# datalogger-v21.net
KiCad netlist of a schematic drawn in EAGLE
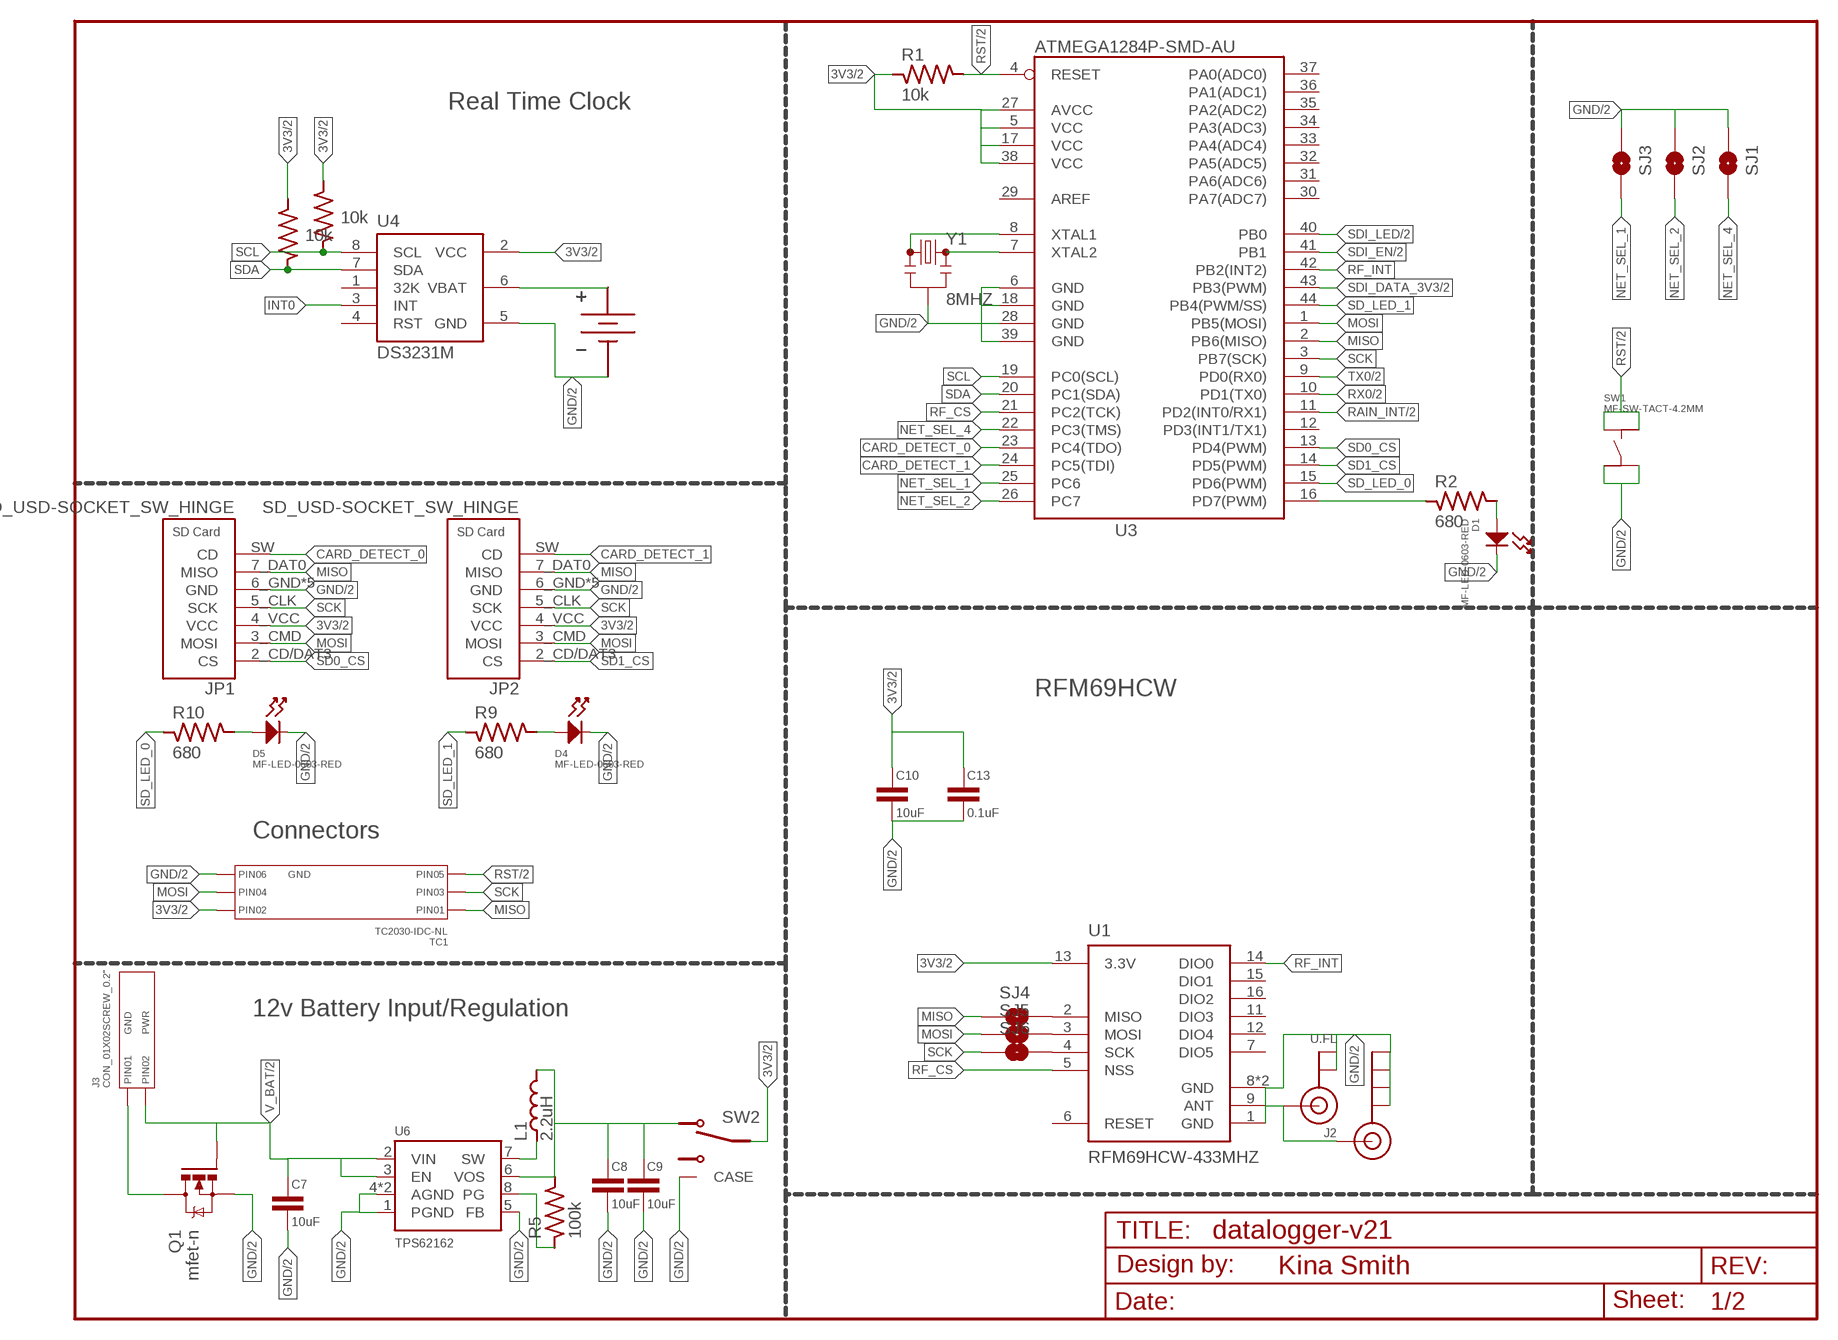
[diagram p0: schematic, sheet 1]
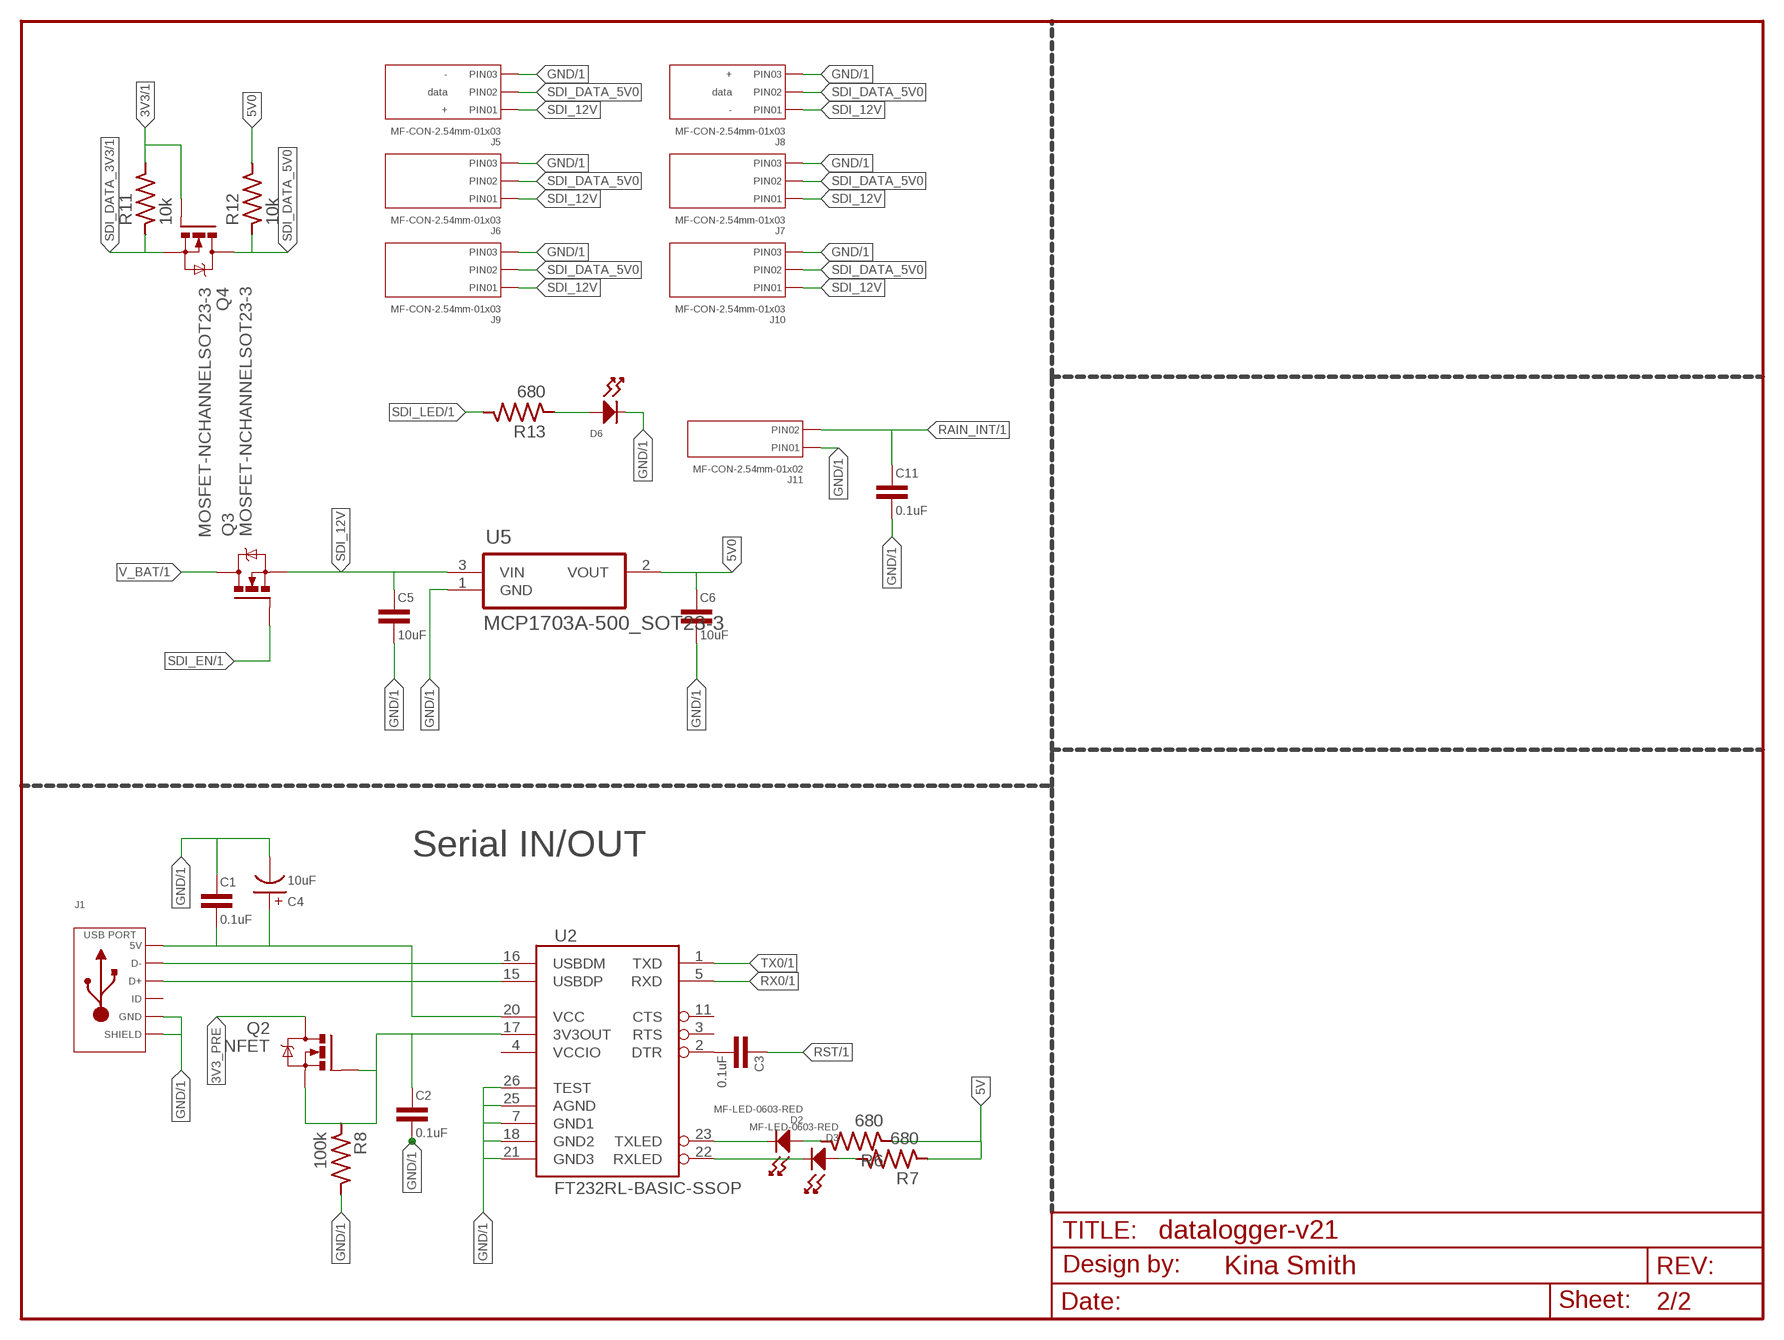
[diagram p1: schematic, sheet 2]

(export (version "E")
  (design (tool "Eeschema 10.0.6"))
  (components
    (comp (ref "BAT1")
      (value "BATTERY_HOLDER12MM")
      (footprint "eagle-import:BAT_12MM")
      (fields (field (name "PARTNO") "BK-885-TR"))
      (libsource (lib "eagle-import") (part "BATTERY_HOLDER12MM"))
    )
    (comp (ref "C7")
      (value "10uF")
      (footprint "eagle-import:C0805-N")
      (fields (field (name "PARTNO") "GRM21BR61C106KE15L"))
      (libsource (lib "eagle-import") (part "CAPACITOR_NP0805-N"))
    )
    (comp (ref "C8")
      (value "10uF")
      (footprint "eagle-import:C0805-N")
      (fields (field (name "PARTNO") "GRM21BR61C106KE15L"))
      (libsource (lib "eagle-import") (part "CAPACITOR_NP0805-N"))
    )
    (comp (ref "C9")
      (value "10uF")
      (footprint "eagle-import:C0805-N")
      (fields (field (name "PARTNO") "GRM21BR61C106KE15L"))
      (libsource (lib "eagle-import") (part "CAPACITOR_NP0805-N"))
    )
    (comp (ref "C10")
      (value "10uF")
      (footprint "eagle-import:C0805-N")
      (fields (field (name "PARTNO") "GRM21BR61C106KE15L"))
      (libsource (lib "eagle-import") (part "CAPACITOR_NP0805-N"))
    )
    (comp (ref "C13")
      (value "0.1uF")
      (footprint "eagle-import:C0603-N")
      (fields (field (name "PARTNO") "CC0603KRX7R7BB104"))
      (libsource (lib "eagle-import") (part "CAPACITOR_NP0603-N"))
    )
    (comp (ref "D1")
      (value "MF-LED-0603-RED")
      (footprint "eagle-import:LED0603")
      (fields (field (name "HOUSEPART") "YES"))
      (libsource (lib "eagle-import") (part "LED_SINGLE-0603-RED"))
    )
    (comp (ref "D4")
      (value "MF-LED-0603-RED")
      (footprint "eagle-import:LED0603")
      (fields (field (name "HOUSEPART") "YES"))
      (libsource (lib "eagle-import") (part "LED_SINGLE-0603-RED"))
    )
    (comp (ref "D5")
      (value "MF-LED-0603-RED")
      (footprint "eagle-import:LED0603")
      (fields (field (name "HOUSEPART") "YES"))
      (libsource (lib "eagle-import") (part "LED_SINGLE-0603-RED"))
    )
    (comp (ref "FRAME1")
      (value "FRAME-LETTERNO_PACKAGE")
      (footprint "eagle-import:DUMMY")
      (fields (field (name "DESIGNER") "Nobody"))
      (libsource (lib "eagle-import") (part "FRAME-LETTERNO_PACKAGE"))
    )
    (comp (ref "J2")
      (value "U.FL")
      (footprint "eagle-import:ADAFRUIT_U.FL")
      (fields (field (name "PARTNO") "U.FL-R-SMT-1(10)"))
      (libsource (lib "eagle-import") (part "ANTENNA_U.FL"))
    )
    (comp (ref "J3")
      (value "CON_01X02SCREW_0.2\"")
      (footprint "eagle-import:SCREW_TERM_2POS")
      (fields (field (name "PARTNO") "1729128"))
      (libsource (lib "eagle-import") (part "CON_01X02SCREW_0.2{dblquote}"))
    )
    (comp (ref "J4")
      (value "ANTENNA_SMA_EDGE")
      (footprint "eagle-import:SMA-EDGE")
      (fields (field (name "PARTNO") "EMPCB.SMAFSTJ.B.HT"))
      (libsource (lib "eagle-import") (part "ANTENNA_SMA_EDGE"))
    )
    (comp (ref "JP1")
      (value "SD_USD-SOCKET_SW_HINGE")
      (footprint "eagle-import:SD_MICRO_HIROSE-DM3C")
      (fields (field (name "PARTNO") "DM3CS-SF "))
      (libsource (lib "eagle-import") (part "SD_USD-SOCKET_SW_HINGE"))
    )
    (comp (ref "JP2")
      (value "SD_USD-SOCKET_SW_HINGE")
      (footprint "eagle-import:SD_MICRO_HIROSE-DM3C")
      (fields (field (name "PARTNO") "DM3CS-SF "))
      (libsource (lib "eagle-import") (part "SD_USD-SOCKET_SW_HINGE"))
    )
    (comp (ref "L1")
      (value "2.2uH")
      (footprint "eagle-import:L2520")
      (fields (field (name "PARTNO") "VLS252012T-2R2M1R3 "))
      (libsource (lib "eagle-import") (part "INDUCTOR2520"))
    )
    (comp (ref "Q1")
      (value "mfet-n")
      (footprint "eagle-import:SOT23-3")
      (fields (field (name "PARTNO") "SI2312BDS-T1-GE3"))
      (libsource (lib "eagle-import") (part "MOSFET-NCHANNELSOT23-3"))
    )
    (comp (ref "R1")
      (value "10k")
      (footprint "eagle-import:R0603-N")
      (fields (field (name "PARTNO") "RC0603FR-0710KL"))
      (libsource (lib "eagle-import") (part "RESISTOR0603-N"))
    )
    (comp (ref "R2")
      (value "680")
      (footprint "eagle-import:R0603-N")
      (fields (field (name "PARTNO") "RC0603FR-0710KL"))
      (libsource (lib "eagle-import") (part "RESISTOR0603-N"))
    )
    (comp (ref "R3")
      (value "10k")
      (footprint "eagle-import:R0603-N")
      (fields (field (name "PARTNO") "RC0603FR-0710KL"))
      (libsource (lib "eagle-import") (part "RESISTOR0603-N"))
    )
    (comp (ref "R4")
      (value "10k")
      (footprint "eagle-import:R0603-N")
      (fields (field (name "PARTNO") "RC0603FR-0710KL"))
      (libsource (lib "eagle-import") (part "RESISTOR0603-N"))
    )
    (comp (ref "R5")
      (value "100k")
      (footprint "eagle-import:R0603-N")
      (fields (field (name "PARTNO") "RC0603FR-07100KL"))
      (libsource (lib "eagle-import") (part "RESISTOR0603-N"))
    )
    (comp (ref "R9")
      (value "680")
      (footprint "eagle-import:R0603-N")
      (fields (field (name "PARTNO") "RC0603FR-0710KL"))
      (libsource (lib "eagle-import") (part "RESISTOR0603-N"))
    )
    (comp (ref "R10")
      (value "680")
      (footprint "eagle-import:R0603-N")
      (fields (field (name "PARTNO") "RC0603FR-0710KL"))
      (libsource (lib "eagle-import") (part "RESISTOR0603-N"))
    )
    (comp (ref "SJ1")
      (value "JUMPER-PAD-2-NOYES_SILK")
      (footprint "eagle-import:PAD-JUMPER-2-NO_YES_SILK")
      (fields (field (name "PARTNO") "NA"))
      (libsource (lib "eagle-import") (part "JUMPER-PAD-2-NOYES_SILK"))
    )
    (comp (ref "SJ2")
      (value "JUMPER-PAD-2-NOYES_SILK")
      (footprint "eagle-import:PAD-JUMPER-2-NO_YES_SILK")
      (fields (field (name "PARTNO") "NA"))
      (libsource (lib "eagle-import") (part "JUMPER-PAD-2-NOYES_SILK"))
    )
    (comp (ref "SJ3")
      (value "JUMPER-PAD-2-NOYES_SILK")
      (footprint "eagle-import:PAD-JUMPER-2-NO_YES_SILK")
      (fields (field (name "PARTNO") "NA"))
      (libsource (lib "eagle-import") (part "JUMPER-PAD-2-NOYES_SILK"))
    )
    (comp (ref "SJ4")
      (value "JUMPER-PAD-2-NOYES_SILK")
      (footprint "eagle-import:PAD-JUMPER-2-NO_YES_SILK")
      (fields (field (name "PARTNO") "NA"))
      (libsource (lib "eagle-import") (part "JUMPER-PAD-2-NOYES_SILK"))
    )
    (comp (ref "SJ5")
      (value "JUMPER-PAD-2-NOYES_SILK")
      (footprint "eagle-import:PAD-JUMPER-2-NO_YES_SILK")
      (fields (field (name "PARTNO") "NA"))
      (libsource (lib "eagle-import") (part "JUMPER-PAD-2-NOYES_SILK"))
    )
    (comp (ref "SJ6")
      (value "JUMPER-PAD-2-NOYES_SILK")
      (footprint "eagle-import:PAD-JUMPER-2-NO_YES_SILK")
      (fields (field (name "PARTNO") "NA"))
      (libsource (lib "eagle-import") (part "JUMPER-PAD-2-NOYES_SILK"))
    )
    (comp (ref "SW1")
      (value "MF-SW-TACT-4.2MM")
      (footprint "eagle-import:TACT4.2MM")
      (fields (field (name "HOUSEPART") "YES") (field (name "PARTNO") "PTS810 SJM 250 SMTR LFS"))
      (libsource (lib "eagle-import") (part "TACT_4.2MM"))
    )
    (comp (ref "SW2")
      (value "SWITCH_SPDT_SMD_ES01MSABE")
      (footprint "eagle-import:SPDT_ES01MSABE")
      (fields (field (name "PARTNO") "ES01MSABE"))
      (libsource (lib "eagle-import") (part "SWITCH_SPDT_SMD_ES01MSABE"))
    )
    (comp (ref "TC1")
      (value "TC2030-IDC-NL")
      (footprint "eagle-import:TC2030-IDC-NL")
      (fields (field (name "HOUSEPART") "NO") (field (name "PARTNO") "NA") (field (name "PARTNO_1") "NA"))
      (libsource (lib "eagle-import") (part "CON_02X03_TC2030-IDC-NL_AVRISP"))
    )
    (comp (ref "U1")
      (value "RFM69HCW-433MHZ")
      (footprint "eagle-import:RFM69HCW-XXXS2")
      (fields (field (name "PARTNO") "COM-13910"))
      (libsource (lib "eagle-import") (part "RFM69HCW-433MHZ"))
    )
    (comp (ref "U3")
      (value "ATMEGA1284P-SMD-AU")
      (footprint "eagle-import:TQFP44")
      (libsource (lib "eagle-import") (part "ATMEGA1284P-SMD-AU"))
    )
    (comp (ref "U4")
      (value "DS3231M")
      (footprint "eagle-import:SO08")
      (fields (field (name "PARTNO") "DS3231MZ/V+"))
      (libsource (lib "eagle-import") (part "DS3231M"))
    )
    (comp (ref "U6")
      (value "TPS62162")
      (footprint "eagle-import:WSON-8")
      (fields (field (name "PARTNO") "TPS62162DSGR"))
      (libsource (lib "eagle-import") (part "TPS62162"))
    )
    (comp (ref "Y1")
      (value "8MHZ")
      (footprint "eagle-import:RESONATOR-SMD")
      (fields (field (name "PARTNO") "CSTCE8M00G55-R0"))
      (libsource (lib "eagle-import") (part "RESONATOR8MHZ"))
    )
    (comp (ref "C1")
      (value "0.1uF")
      (footprint "eagle-import:C0603-N")
      (libsource (lib "eagle-import") (part "CAPACITOR_NP0603-N"))
    )
    (comp (ref "C2")
      (value "0.1uF")
      (footprint "eagle-import:C0603-N")
      (libsource (lib "eagle-import") (part "CAPACITOR_NP0603-N"))
    )
    (comp (ref "C3")
      (value "0.1uF")
      (footprint "eagle-import:C0603-N")
      (libsource (lib "eagle-import") (part "CAPACITOR_NP0603-N"))
    )
    (comp (ref "C4")
      (value "10uF")
      (footprint "eagle-import:EIA3216")
      (libsource (lib "eagle-import") (part "CAPACITOR_P_3216"))
    )
    (comp (ref "C5")
      (value "10uF")
      (footprint "eagle-import:C0805-N")
      (libsource (lib "eagle-import") (part "CAPACITOR_NP0805-N"))
    )
    (comp (ref "C6")
      (value "10uF")
      (footprint "eagle-import:C0805-N")
      (libsource (lib "eagle-import") (part "CAPACITOR_NP0805-N"))
    )
    (comp (ref "C11")
      (value "0.1uF")
      (footprint "eagle-import:C0603-N")
      (libsource (lib "eagle-import") (part "CAPACITOR_NP0603-N"))
    )
    (comp (ref "D2")
      (value "MF-LED-0603-RED")
      (footprint "eagle-import:LED0603")
      (fields (field (name "HOUSEPART") "YES"))
      (libsource (lib "eagle-import") (part "LED_SINGLE-0603-RED"))
    )
    (comp (ref "D3")
      (value "MF-LED-0603-RED")
      (footprint "eagle-import:LED0603")
      (fields (field (name "HOUSEPART") "YES"))
      (libsource (lib "eagle-import") (part "LED_SINGLE-0603-RED"))
    )
    (comp (ref "D6")
      (value "LED_SINGLE-0603")
      (footprint "eagle-import:LED0603")
      (fields (field (name "HOUSEPART") "NO"))
      (libsource (lib "eagle-import") (part "LED_SINGLE-0603"))
    )
    (comp (ref "FRAME3")
      (value "FRAME-LETTERNO_PACKAGE")
      (footprint "eagle-import:DUMMY")
      (fields (field (name "DESIGNER") "Nobody"))
      (libsource (lib "eagle-import") (part "FRAME-LETTERNO_PACKAGE"))
    )
    (comp (ref "J1")
      (value "USB-5PIN_B-MICRO_R/A_STRONG")
      (footprint "eagle-import:USB-MICRO-MOLEX-105017-0001")
      (fields (field (name "PARTNO") "1050170001"))
      (libsource (lib "eagle-import") (part "USB-5PIN_B-MICRO_R/A_STRONG"))
    )
    (comp (ref "J5")
      (value "MF-CON-2.54mm-01x03")
      (footprint "eagle-import:PTH_2.54MM_01X03")
      (fields
        (field (name "HOUSEPART") "YES")
        (field (name "LABEL01") "+")
        (field (name "LABEL02") "data")
        (field (name "LABEL03") "-")
      )
      (libsource (lib "eagle-import") (part "CON_01X03_PTH_2.54MM"))
    )
    (comp (ref "J6")
      (value "MF-CON-2.54mm-01x03")
      (footprint "eagle-import:PTH_2.54MM_01X03")
      (fields (field (name "HOUSEPART") "YES"))
      (libsource (lib "eagle-import") (part "CON_01X03_PTH_2.54MM"))
    )
    (comp (ref "J7")
      (value "MF-CON-2.54mm-01x03")
      (footprint "eagle-import:PTH_2.54MM_01X03")
      (fields (field (name "HOUSEPART") "YES"))
      (libsource (lib "eagle-import") (part "CON_01X03_PTH_2.54MM"))
    )
    (comp (ref "J8")
      (value "MF-CON-2.54mm-01x03")
      (footprint "eagle-import:PTH_2.54MM_01X03")
      (fields
        (field (name "HOUSEPART") "YES")
        (field (name "LABEL01") "-")
        (field (name "LABEL02") "data")
        (field (name "LABEL03") "+")
      )
      (libsource (lib "eagle-import") (part "CON_01X03_PTH_2.54MM"))
    )
    (comp (ref "J9")
      (value "MF-CON-2.54mm-01x03")
      (footprint "eagle-import:PTH_2.54MM_01X03")
      (fields (field (name "HOUSEPART") "YES"))
      (libsource (lib "eagle-import") (part "CON_01X03_PTH_2.54MM"))
    )
    (comp (ref "J10")
      (value "MF-CON-2.54mm-01x03")
      (footprint "eagle-import:PTH_2.54MM_01X03")
      (fields (field (name "HOUSEPART") "YES"))
      (libsource (lib "eagle-import") (part "CON_01X03_PTH_2.54MM"))
    )
    (comp (ref "J11")
      (value "MF-CON-2.54mm-01x02")
      (footprint "eagle-import:PTH_2.54MM_01X02")
      (fields (field (name "HOUSEPART") "YES"))
      (libsource (lib "eagle-import") (part "CON_01X02_PTH_2.54MM"))
    )
    (comp (ref "Q2")
      (value "NFET")
      (footprint "eagle-import:SOT23-3")
      (libsource (lib "eagle-import") (part "MOSFET-NCHANNELSOT23-3"))
    )
    (comp (ref "Q3")
      (value "MOSFET-NCHANNELSOT23-3")
      (footprint "eagle-import:SOT23-3")
      (libsource (lib "eagle-import") (part "MOSFET-NCHANNELSOT23-3"))
    )
    (comp (ref "Q4")
      (value "MOSFET-NCHANNELSOT23-3")
      (footprint "eagle-import:SOT23-3")
      (libsource (lib "eagle-import") (part "MOSFET-NCHANNELSOT23-3"))
    )
    (comp (ref "R6")
      (value "680")
      (footprint "eagle-import:R0603-N")
      (libsource (lib "eagle-import") (part "RESISTOR0603-N"))
    )
    (comp (ref "R7")
      (value "680")
      (footprint "eagle-import:R0603-N")
      (libsource (lib "eagle-import") (part "RESISTOR0603-N"))
    )
    (comp (ref "R8")
      (value "100k")
      (footprint "eagle-import:R0603-N")
      (libsource (lib "eagle-import") (part "RESISTOR0603-N"))
    )
    (comp (ref "R11")
      (value "10k")
      (footprint "eagle-import:R0603-N")
      (libsource (lib "eagle-import") (part "RESISTOR0603-N"))
    )
    (comp (ref "R12")
      (value "10k")
      (footprint "eagle-import:R0603-N")
      (libsource (lib "eagle-import") (part "RESISTOR0603-N"))
    )
    (comp (ref "R13")
      (value "680")
      (footprint "eagle-import:R0603-N")
      (libsource (lib "eagle-import") (part "RESISTOR0603-N"))
    )
    (comp (ref "U2")
      (value "FT232RL-BASIC-SSOP")
      (footprint "eagle-import:SSOP28")
      (libsource (lib "eagle-import") (part "FT232RL-BASIC-SSOP"))
    )
    (comp (ref "U5")
      (value "MCP1703A-500_SOT23-3")
      (footprint "eagle-import:SOT23-3")
      (fields (field (name "PARTNO") "MCP1703AT-5002E/CB"))
      (libsource (lib "eagle-import") (part "MCP1703A-500_SOT23-3"))
    )
  )
  (nets
    (net (code "1") (name "3V3") (class "Default")
      (node (ref "C10") (pin "1") (pinfunction "1_1") (pintype "passive"))
      (node (ref "C13") (pin "1") (pinfunction "1_1") (pintype "passive"))
      (node (ref "JP1") (pin "4_VCC") (pinfunction "VCC_4_VCC") (pintype "bidirectional"))
      (node (ref "JP2") (pin "4_VCC") (pinfunction "VCC_4_VCC") (pintype "bidirectional"))
      (node (ref "Q4") (pin "1") (pinfunction "G_1") (pintype "passive"))
      (node (ref "R1") (pin "1") (pinfunction "P$1_1") (pintype "passive"))
      (node (ref "R11") (pin "2") (pinfunction "P$2_2") (pintype "passive"))
      (node (ref "R3") (pin "2") (pinfunction "P$2_2") (pintype "passive"))
      (node (ref "R4") (pin "2") (pinfunction "P$2_2") (pintype "passive"))
      (node (ref "SW2") (pin "2") (pinfunction "COM_2") (pintype "bidirectional"))
      (node (ref "TC1") (pin "P$2") (pinfunction "PIN2_P$2") (pintype "bidirectional"))
      (node (ref "U1") (pin "13") (pinfunction "3.3V_13") (pintype "power_in"))
      (node (ref "U3") (pin "17") (pinfunction "VCC_17") (pintype "bidirectional"))
      (node (ref "U3") (pin "27") (pinfunction "AVCC_27") (pintype "bidirectional"))
      (node (ref "U3") (pin "38") (pinfunction "VCC_38") (pintype "bidirectional"))
      (node (ref "U3") (pin "5") (pinfunction "VCC_5") (pintype "bidirectional"))
      (node (ref "U4") (pin "2") (pinfunction "VCC_2") (pintype "power_in"))
    )
    (net (code "2") (name "3V3_PRE") (class "Default")
      (node (ref "C8") (pin "1") (pinfunction "1_1") (pintype "passive"))
      (node (ref "C9") (pin "1") (pinfunction "1_1") (pintype "passive"))
      (node (ref "L1") (pin "P$2") (pinfunction "P$2_P$2") (pintype "passive"))
      (node (ref "Q2") (pin "3") (pinfunction "D_3") (pintype "passive"))
      (node (ref "R5") (pin "2") (pinfunction "P$2_2") (pintype "passive"))
      (node (ref "SW2") (pin "1") (pinfunction "1_1") (pintype "bidirectional"))
      (node (ref "U6") (pin "6") (pinfunction "VOS_6") (pintype "bidirectional"))
    )
    (net (code "3") (name "5V") (class "Default")
      (node (ref "C1") (pin "2") (pinfunction "2_2") (pintype "passive"))
      (node (ref "C4") (pin "A") (pinfunction "POS_A") (pintype "passive"))
      (node (ref "J1") (pin "1") (pinfunction "5V_1") (pintype "power_in"))
      (node (ref "R6") (pin "1") (pinfunction "P$1_1") (pintype "passive"))
      (node (ref "R7") (pin "1") (pinfunction "P$1_1") (pintype "passive"))
      (node (ref "U2") (pin "20") (pinfunction "VCC_20") (pintype "power_in"))
    )
    (net (code "4") (name "5V0") (class "Default")
      (node (ref "C6") (pin "1") (pinfunction "1_1") (pintype "passive"))
      (node (ref "R12") (pin "2") (pinfunction "P$2_2") (pintype "passive"))
      (node (ref "U5") (pin "2") (pinfunction "VOUT_2") (pintype "output"))
    )
    (net (code "5") (name "CARD_DETECT_0") (class "Default")
      (node (ref "JP1") (pin "SW") (pinfunction "CD_SW") (pintype "bidirectional"))
      (node (ref "U3") (pin "23") (pinfunction "PC4(TDO)_23") (pintype "bidirectional"))
    )
    (net (code "6") (name "CARD_DETECT_1") (class "Default")
      (node (ref "JP2") (pin "SW") (pinfunction "CD_SW") (pintype "bidirectional"))
      (node (ref "U3") (pin "24") (pinfunction "PC5(TDI)_24") (pintype "bidirectional"))
    )
    (net (code "7") (name "GND") (class "Default")
      (node (ref "BAT1") (pin "GND") (pinfunction "GND_GND") (pintype "bidirectional"))
      (node (ref "C1") (pin "1") (pinfunction "1_1") (pintype "passive"))
      (node (ref "C10") (pin "2") (pinfunction "2_2") (pintype "passive"))
      (node (ref "C11") (pin "2") (pinfunction "2_2") (pintype "passive"))
      (node (ref "C13") (pin "2") (pinfunction "2_2") (pintype "passive"))
      (node (ref "C2") (pin "2") (pinfunction "2_2") (pintype "passive"))
      (node (ref "C4") (pin "C") (pinfunction "NEG_C") (pintype "passive"))
      (node (ref "C5") (pin "2") (pinfunction "2_2") (pintype "passive"))
      (node (ref "C6") (pin "2") (pinfunction "2_2") (pintype "passive"))
      (node (ref "C7") (pin "2") (pinfunction "2_2") (pintype "passive"))
      (node (ref "C8") (pin "2") (pinfunction "2_2") (pintype "passive"))
      (node (ref "C9") (pin "2") (pinfunction "2_2") (pintype "passive"))
      (node (ref "D1") (pin "CATHODE") (pinfunction "CATHODE_CATHODE") (pintype "power_in"))
      (node (ref "D4") (pin "CATHODE") (pinfunction "CATHODE_CATHODE") (pintype "power_in"))
      (node (ref "D5") (pin "CATHODE") (pinfunction "CATHODE_CATHODE") (pintype "power_in"))
      (node (ref "D6") (pin "CATHODE") (pinfunction "CATHODE_CATHODE") (pintype "power_in"))
      (node (ref "J1") (pin "5") (pinfunction "GND_5") (pintype "power_in"))
      (node (ref "J1") (pin "P$1") (pinfunction "SLD_P$1") (pintype "power_in"))
      (node (ref "J1") (pin "P$2") (pinfunction "SLD_P$2") (pintype "power_in"))
      (node (ref "J1") (pin "P$3") (pinfunction "SLD_P$3") (pintype "power_in"))
      (node (ref "J1") (pin "P$4") (pinfunction "SLD_P$4") (pintype "power_in"))
      (node (ref "J1") (pin "P$5") (pinfunction "SLD_P$5") (pintype "power_in"))
      (node (ref "J1") (pin "P$6") (pinfunction "SLD_P$6") (pintype "power_in"))
      (node (ref "J10") (pin "P$3") (pinfunction "PIN3_P$3") (pintype "bidirectional"))
      (node (ref "J11") (pin "P$1") (pinfunction "PIN1_P$1") (pintype "bidirectional"))
      (node (ref "J2") (pin "1") (pinfunction "GND_1") (pintype "passive"))
      (node (ref "J2") (pin "2") (pinfunction "GND_2") (pintype "passive"))
      (node (ref "J4") (pin "GND@0") (pinfunction "GND_GND@0") (pintype "bidirectional"))
      (node (ref "J4") (pin "GND@1") (pinfunction "GND_GND@1") (pintype "bidirectional"))
      (node (ref "J4") (pin "GND@2") (pinfunction "GND_GND@2") (pintype "bidirectional"))
      (node (ref "J4") (pin "GND@3") (pinfunction "GND_GND@3") (pintype "bidirectional"))
      (node (ref "J5") (pin "P$3") (pinfunction "PIN3_P$3") (pintype "bidirectional"))
      (node (ref "J6") (pin "P$3") (pinfunction "PIN3_P$3") (pintype "bidirectional"))
      (node (ref "J7") (pin "P$3") (pinfunction "PIN3_P$3") (pintype "bidirectional"))
      (node (ref "J8") (pin "P$3") (pinfunction "PIN3_P$3") (pintype "bidirectional"))
      (node (ref "J9") (pin "P$3") (pinfunction "PIN3_P$3") (pintype "bidirectional"))
      (node (ref "JP1") (pin "6_GND") (pinfunction "GND_6_GND") (pintype "bidirectional"))
      (node (ref "JP1") (pin "GND1") (pinfunction "GND_GND1") (pintype "bidirectional"))
      (node (ref "JP1") (pin "GND2") (pinfunction "GND_GND2") (pintype "bidirectional"))
      (node (ref "JP1") (pin "GND3") (pinfunction "GND_GND3") (pintype "bidirectional"))
      (node (ref "JP1") (pin "GND4") (pinfunction "GND_GND4") (pintype "bidirectional"))
      (node (ref "JP2") (pin "6_GND") (pinfunction "GND_6_GND") (pintype "bidirectional"))
      (node (ref "JP2") (pin "GND1") (pinfunction "GND_GND1") (pintype "bidirectional"))
      (node (ref "JP2") (pin "GND2") (pinfunction "GND_GND2") (pintype "bidirectional"))
      (node (ref "JP2") (pin "GND3") (pinfunction "GND_GND3") (pintype "bidirectional"))
      (node (ref "JP2") (pin "GND4") (pinfunction "GND_GND4") (pintype "bidirectional"))
      (node (ref "Q1") (pin "2") (pinfunction "S_2") (pintype "passive"))
      (node (ref "R8") (pin "2") (pinfunction "P$2_2") (pintype "passive"))
      (node (ref "SJ1") (pin "1") (pinfunction "1_1") (pintype "passive"))
      (node (ref "SJ2") (pin "1") (pinfunction "1_1") (pintype "passive"))
      (node (ref "SJ3") (pin "1") (pinfunction "1_1") (pintype "passive"))
      (node (ref "SW1") (pin "P$3") (pinfunction "P$3_P$3") (pintype "bidirectional"))
      (node (ref "SW1") (pin "P$4") (pinfunction "P$4_P$4") (pintype "bidirectional"))
      (node (ref "SW2") (pin "GND") (pinfunction "CASE_GND") (pintype "bidirectional"))
      (node (ref "SW2") (pin "GND1") (pinfunction "CASE_GND1") (pintype "bidirectional"))
      (node (ref "TC1") (pin "P$6") (pinfunction "PIN6_P$6") (pintype "bidirectional"))
      (node (ref "U1") (pin "1") (pinfunction "GND_1") (pintype "power_in"))
      (node (ref "U1") (pin "10") (pinfunction "GND_10") (pintype "power_in"))
      (node (ref "U1") (pin "8") (pinfunction "GND_8") (pintype "power_in"))
      (node (ref "U2") (pin "18") (pinfunction "GND2_18") (pintype "power_in"))
      (node (ref "U2") (pin "21") (pinfunction "GND3_21") (pintype "power_in"))
      (node (ref "U2") (pin "25") (pinfunction "AGND_25") (pintype "power_in"))
      (node (ref "U2") (pin "26") (pinfunction "TEST_26") (pintype "input"))
      (node (ref "U2") (pin "7") (pinfunction "GND1_7") (pintype "power_in"))
      (node (ref "U3") (pin "18") (pinfunction "GND_18") (pintype "bidirectional"))
      (node (ref "U3") (pin "28") (pinfunction "GND_28") (pintype "bidirectional"))
      (node (ref "U3") (pin "39") (pinfunction "GND_39") (pintype "bidirectional"))
      (node (ref "U3") (pin "6") (pinfunction "GND_6") (pintype "bidirectional"))
      (node (ref "U4") (pin "5") (pinfunction "GND_5") (pintype "power_in"))
      (node (ref "U5") (pin "1") (pinfunction "GND_1") (pintype "passive"))
      (node (ref "U6") (pin "1") (pinfunction "PGND_1") (pintype "bidirectional"))
      (node (ref "U6") (pin "4") (pinfunction "AGND_4") (pintype "bidirectional"))
      (node (ref "U6") (pin "5") (pinfunction "FB_5") (pintype "bidirectional"))
      (node (ref "U6") (pin "P$9") (pinfunction "AGND_P$9") (pintype "bidirectional"))
      (node (ref "Y1") (pin "2") (pinfunction "2_2") (pintype "passive"))
    )
    (net (code "8") (name "INT0") (class "Default")
      (node (ref "U4") (pin "3") (pinfunction "INT_3") (pintype "bidirectional"))
    )
    (net (code "9") (name "MISO") (class "Default")
      (node (ref "JP1") (pin "7_DAT0") (pinfunction "MISO_7_DAT0") (pintype "bidirectional"))
      (node (ref "JP2") (pin "7_DAT0") (pinfunction "MISO_7_DAT0") (pintype "bidirectional"))
      (node (ref "SJ4") (pin "1") (pinfunction "1_1") (pintype "passive"))
      (node (ref "TC1") (pin "P$1") (pinfunction "PIN1_P$1") (pintype "bidirectional"))
      (node (ref "U3") (pin "2") (pinfunction "PB6(MISO)_2") (pintype "bidirectional"))
    )
    (net (code "10") (name "MOSI") (class "Default")
      (node (ref "JP1") (pin "3_CMD") (pinfunction "MOSI_3_CMD") (pintype "bidirectional"))
      (node (ref "JP2") (pin "3_CMD") (pinfunction "MOSI_3_CMD") (pintype "bidirectional"))
      (node (ref "SJ5") (pin "1") (pinfunction "1_1") (pintype "passive"))
      (node (ref "TC1") (pin "P$4") (pinfunction "PIN4_P$4") (pintype "bidirectional"))
      (node (ref "U3") (pin "1") (pinfunction "PB5(MOSI)_1") (pintype "bidirectional"))
    )
    (net (code "11") (name "NET_SEL_1") (class "Default")
      (node (ref "SJ3") (pin "2") (pinfunction "2_2") (pintype "passive"))
      (node (ref "U3") (pin "25") (pinfunction "PC6_25") (pintype "bidirectional"))
    )
    (net (code "12") (name "NET_SEL_2") (class "Default")
      (node (ref "SJ2") (pin "2") (pinfunction "2_2") (pintype "passive"))
      (node (ref "U3") (pin "26") (pinfunction "PC7_26") (pintype "bidirectional"))
    )
    (net (code "13") (name "NET_SEL_4") (class "Default")
      (node (ref "SJ1") (pin "2") (pinfunction "2_2") (pintype "passive"))
      (node (ref "U3") (pin "22") (pinfunction "PC3(TMS)_22") (pintype "bidirectional"))
    )
    (net (code "14") (name "Net-(J1-D+)") (class "Default")
      (node (ref "J1") (pin "3") (pinfunction "D+_3") (pintype "bidirectional"))
      (node (ref "U2") (pin "15") (pinfunction "USBDP_15") (pintype "bidirectional"))
    )
    (net (code "15") (name "Net-(J1-D-)") (class "Default")
      (node (ref "J1") (pin "2") (pinfunction "D-_2") (pintype "bidirectional"))
      (node (ref "U2") (pin "16") (pinfunction "USBDM_16") (pintype "bidirectional"))
    )
    (net (code "16") (name "Net-(J2-SIGNAL)") (class "Default")
      (node (ref "J2") (pin "3") (pinfunction "SIGNAL_3") (pintype "passive"))
      (node (ref "J4") (pin "SIG") (pinfunction "SIGNAL_SIG") (pintype "bidirectional"))
      (node (ref "U1") (pin "9") (pinfunction "ANT_9") (pintype "passive"))
    )
    (net (code "17") (name "Net-(J3-PIN1)") (class "Default")
      (node (ref "J3") (pin "GND") (pinfunction "PIN1_GND") (pintype "bidirectional"))
      (node (ref "Q1") (pin "3") (pinfunction "D_3") (pintype "passive"))
    )
    (net (code "18") (name "Net-(Q2-G)") (class "Default")
      (node (ref "C2") (pin "1") (pinfunction "1_1") (pintype "passive"))
      (node (ref "Q2") (pin "1") (pinfunction "G_1") (pintype "passive"))
      (node (ref "Q2") (pin "2") (pinfunction "S_2") (pintype "passive"))
      (node (ref "R8") (pin "1") (pinfunction "P$1_1") (pintype "passive"))
      (node (ref "U2") (pin "17") (pinfunction "3V3OUT_17") (pintype "output"))
    )
    (net (code "19") (name "Net-(R2-P$1)") (class "Default")
      (node (ref "R2") (pin "1") (pinfunction "P$1_1") (pintype "passive"))
      (node (ref "U3") (pin "16") (pinfunction "PD7(PWM)_16") (pintype "bidirectional"))
    )
    (net (code "20") (name "Net-(R2-P$2)") (class "Default")
      (node (ref "D1") (pin "ANODE") (pinfunction "ANODE_ANODE") (pintype "power_in"))
      (node (ref "R2") (pin "2") (pinfunction "P$2_2") (pintype "passive"))
    )
    (net (code "21") (name "Net-(R5-P$1)") (class "Default")
      (node (ref "R5") (pin "1") (pinfunction "P$1_1") (pintype "passive"))
      (node (ref "U6") (pin "8") (pinfunction "PG_8") (pintype "bidirectional"))
    )
    (net (code "22") (name "Net-(R6-P$2)") (class "Default")
      (node (ref "D2") (pin "ANODE") (pinfunction "ANODE_ANODE") (pintype "power_in"))
      (node (ref "R6") (pin "2") (pinfunction "P$2_2") (pintype "passive"))
    )
    (net (code "23") (name "Net-(R7-P$2)") (class "Default")
      (node (ref "D3") (pin "ANODE") (pinfunction "ANODE_ANODE") (pintype "power_in"))
      (node (ref "R7") (pin "2") (pinfunction "P$2_2") (pintype "passive"))
    )
    (net (code "24") (name "Net-(R9-P$2)") (class "Default")
      (node (ref "D4") (pin "ANODE") (pinfunction "ANODE_ANODE") (pintype "power_in"))
      (node (ref "R9") (pin "2") (pinfunction "P$2_2") (pintype "passive"))
    )
    (net (code "25") (name "Net-(R10-P$2)") (class "Default")
      (node (ref "D5") (pin "ANODE") (pinfunction "ANODE_ANODE") (pintype "power_in"))
      (node (ref "R10") (pin "2") (pinfunction "P$2_2") (pintype "passive"))
    )
    (net (code "26") (name "Net-(R13-P$1)") (class "Default")
      (node (ref "D6") (pin "ANODE") (pinfunction "ANODE_ANODE") (pintype "power_in"))
      (node (ref "R13") (pin "1") (pinfunction "P$1_1") (pintype "passive"))
    )
    (net (code "27") (name "Net-(U1-MISO)") (class "Default")
      (node (ref "SJ4") (pin "2") (pinfunction "2_2") (pintype "passive"))
      (node (ref "U1") (pin "2") (pinfunction "MISO_2") (pintype "bidirectional"))
    )
    (net (code "28") (name "Net-(U1-MOSI)") (class "Default")
      (node (ref "SJ5") (pin "2") (pinfunction "2_2") (pintype "passive"))
      (node (ref "U1") (pin "3") (pinfunction "MOSI_3") (pintype "input"))
    )
    (net (code "29") (name "Net-(U1-SCK)") (class "Default")
      (node (ref "SJ6") (pin "2") (pinfunction "2_2") (pintype "passive"))
      (node (ref "U1") (pin "4") (pinfunction "SCK_4") (pintype "input"))
    )
    (net (code "30") (name "Net-(U2-DTR)") (class "Default")
      (node (ref "C3") (pin "2") (pinfunction "2_2") (pintype "passive"))
      (node (ref "U2") (pin "2") (pinfunction "DTR_2") (pintype "bidirectional"))
    )
    (net (code "31") (name "Net-(U2-RXLED)") (class "Default")
      (node (ref "D3") (pin "CATHODE") (pinfunction "CATHODE_CATHODE") (pintype "power_in"))
      (node (ref "U2") (pin "22") (pinfunction "RXLED_22") (pintype "bidirectional"))
    )
    (net (code "32") (name "Net-(U2-TXLED)") (class "Default")
      (node (ref "D2") (pin "CATHODE") (pinfunction "CATHODE_CATHODE") (pintype "power_in"))
      (node (ref "U2") (pin "23") (pinfunction "TXLED_23") (pintype "bidirectional"))
    )
    (net (code "33") (name "Net-(U3-XTAL1)") (class "Default")
      (node (ref "U3") (pin "8") (pinfunction "XTAL1_8") (pintype "bidirectional"))
      (node (ref "Y1") (pin "1") (pinfunction "1_1") (pintype "passive"))
    )
    (net (code "34") (name "Net-(U3-XTAL2)") (class "Default")
      (node (ref "U3") (pin "7") (pinfunction "XTAL2_7") (pintype "bidirectional"))
      (node (ref "Y1") (pin "3") (pinfunction "3_3") (pintype "passive"))
    )
    (net (code "35") (name "Net-(U4-VBAT)") (class "Default")
      (node (ref "BAT1") (pin "PWR@1") (pinfunction "VBAT_PWR@1") (pintype "bidirectional"))
      (node (ref "BAT1") (pin "PWR@2") (pinfunction "VBAT_PWR@2") (pintype "bidirectional"))
      (node (ref "U4") (pin "6") (pinfunction "VBAT_6") (pintype "power_in"))
    )
    (net (code "36") (name "Net-(U6-SW)") (class "Default")
      (node (ref "L1") (pin "P$1") (pinfunction "P$1_P$1") (pintype "passive"))
      (node (ref "U6") (pin "7") (pinfunction "SW_7") (pintype "bidirectional"))
    )
    (net (code "37") (name "RAIN_INT") (class "Default")
      (node (ref "C11") (pin "1") (pinfunction "1_1") (pintype "passive"))
      (node (ref "J11") (pin "P$2") (pinfunction "PIN2_P$2") (pintype "bidirectional"))
      (node (ref "U3") (pin "11") (pinfunction "PD2(INT0/RX1)_11") (pintype "bidirectional"))
    )
    (net (code "38") (name "RF_CS") (class "Default")
      (node (ref "U1") (pin "5") (pinfunction "NSS_5") (pintype "input"))
      (node (ref "U3") (pin "21") (pinfunction "PC2(TCK)_21") (pintype "bidirectional"))
    )
    (net (code "39") (name "RF_INT") (class "Default")
      (node (ref "U1") (pin "14") (pinfunction "DIO0_14") (pintype "bidirectional"))
      (node (ref "U3") (pin "42") (pinfunction "PB2(INT2)_42") (pintype "bidirectional"))
    )
    (net (code "40") (name "RST") (class "Default")
      (node (ref "C3") (pin "1") (pinfunction "1_1") (pintype "passive"))
      (node (ref "R1") (pin "2") (pinfunction "P$2_2") (pintype "passive"))
      (node (ref "SW1") (pin "P$1") (pinfunction "P$1_P$1") (pintype "bidirectional"))
      (node (ref "SW1") (pin "P$2") (pinfunction "P$2_P$2") (pintype "bidirectional"))
      (node (ref "TC1") (pin "P$5") (pinfunction "PIN5_P$5") (pintype "bidirectional"))
      (node (ref "U3") (pin "4") (pinfunction "RESET_4") (pintype "bidirectional"))
    )
    (net (code "41") (name "RX0") (class "Default")
      (node (ref "U2") (pin "5") (pinfunction "RXD_5") (pintype "input"))
      (node (ref "U3") (pin "10") (pinfunction "PD1(TX0)_10") (pintype "bidirectional"))
    )
    (net (code "42") (name "SCK") (class "Default")
      (node (ref "JP1") (pin "5_CLK") (pinfunction "SCK_5_CLK") (pintype "bidirectional"))
      (node (ref "JP2") (pin "5_CLK") (pinfunction "SCK_5_CLK") (pintype "bidirectional"))
      (node (ref "SJ6") (pin "1") (pinfunction "1_1") (pintype "passive"))
      (node (ref "TC1") (pin "P$3") (pinfunction "PIN3_P$3") (pintype "bidirectional"))
      (node (ref "U3") (pin "3") (pinfunction "PB7(SCK)_3") (pintype "bidirectional"))
    )
    (net (code "43") (name "SCL") (class "Default")
      (node (ref "R3") (pin "1") (pinfunction "P$1_1") (pintype "passive"))
      (node (ref "U3") (pin "19") (pinfunction "PC0(SCL)_19") (pintype "bidirectional"))
      (node (ref "U4") (pin "8") (pinfunction "SCL_8") (pintype "bidirectional"))
    )
    (net (code "44") (name "SD0_CS") (class "Default")
      (node (ref "JP1") (pin "2_CD/DAT3") (pinfunction "CS_2_CD/DAT3") (pintype "bidirectional"))
      (node (ref "U3") (pin "13") (pinfunction "PD4(PWM)_13") (pintype "bidirectional"))
    )
    (net (code "45") (name "SD1_CS") (class "Default")
      (node (ref "JP2") (pin "2_CD/DAT3") (pinfunction "CS_2_CD/DAT3") (pintype "bidirectional"))
      (node (ref "U3") (pin "14") (pinfunction "PD5(PWM)_14") (pintype "bidirectional"))
    )
    (net (code "46") (name "SDA") (class "Default")
      (node (ref "R4") (pin "1") (pinfunction "P$1_1") (pintype "passive"))
      (node (ref "U3") (pin "20") (pinfunction "PC1(SDA)_20") (pintype "bidirectional"))
      (node (ref "U4") (pin "7") (pinfunction "SDA_7") (pintype "bidirectional"))
    )
    (net (code "47") (name "SDI_12V") (class "Default")
      (node (ref "C5") (pin "1") (pinfunction "1_1") (pintype "passive"))
      (node (ref "J10") (pin "P$1") (pinfunction "PIN1_P$1") (pintype "bidirectional"))
      (node (ref "J5") (pin "P$1") (pinfunction "PIN1_P$1") (pintype "bidirectional"))
      (node (ref "J6") (pin "P$1") (pinfunction "PIN1_P$1") (pintype "bidirectional"))
      (node (ref "J7") (pin "P$1") (pinfunction "PIN1_P$1") (pintype "bidirectional"))
      (node (ref "J8") (pin "P$1") (pinfunction "PIN1_P$1") (pintype "bidirectional"))
      (node (ref "J9") (pin "P$1") (pinfunction "PIN1_P$1") (pintype "bidirectional"))
      (node (ref "Q3") (pin "2") (pinfunction "S_2") (pintype "passive"))
      (node (ref "U5") (pin "3") (pinfunction "VIN_3") (pintype "input"))
    )
    (net (code "48") (name "SDI_DATA_3V3") (class "Default")
      (node (ref "Q4") (pin "2") (pinfunction "S_2") (pintype "passive"))
      (node (ref "R11") (pin "1") (pinfunction "P$1_1") (pintype "passive"))
      (node (ref "U3") (pin "43") (pinfunction "PB3(PWM)_43") (pintype "bidirectional"))
    )
    (net (code "49") (name "SDI_DATA_5V0") (class "Default")
      (node (ref "J10") (pin "P$2") (pinfunction "PIN2_P$2") (pintype "bidirectional"))
      (node (ref "J5") (pin "P$2") (pinfunction "PIN2_P$2") (pintype "bidirectional"))
      (node (ref "J6") (pin "P$2") (pinfunction "PIN2_P$2") (pintype "bidirectional"))
      (node (ref "J7") (pin "P$2") (pinfunction "PIN2_P$2") (pintype "bidirectional"))
      (node (ref "J8") (pin "P$2") (pinfunction "PIN2_P$2") (pintype "bidirectional"))
      (node (ref "J9") (pin "P$2") (pinfunction "PIN2_P$2") (pintype "bidirectional"))
      (node (ref "Q4") (pin "3") (pinfunction "D_3") (pintype "passive"))
      (node (ref "R12") (pin "1") (pinfunction "P$1_1") (pintype "passive"))
    )
    (net (code "50") (name "SDI_EN") (class "Default")
      (node (ref "Q3") (pin "1") (pinfunction "G_1") (pintype "passive"))
      (node (ref "U3") (pin "41") (pinfunction "PB1_41") (pintype "bidirectional"))
    )
    (net (code "51") (name "SDI_LED") (class "Default")
      (node (ref "R13") (pin "2") (pinfunction "P$2_2") (pintype "passive"))
      (node (ref "U3") (pin "40") (pinfunction "PB0_40") (pintype "bidirectional"))
    )
    (net (code "52") (name "SD_LED_0") (class "Default")
      (node (ref "R10") (pin "1") (pinfunction "P$1_1") (pintype "passive"))
      (node (ref "U3") (pin "15") (pinfunction "PD6(PWM)_15") (pintype "bidirectional"))
    )
    (net (code "53") (name "SD_LED_1") (class "Default")
      (node (ref "R9") (pin "1") (pinfunction "P$1_1") (pintype "passive"))
      (node (ref "U3") (pin "44") (pinfunction "PB4(PWM/SS)_44") (pintype "bidirectional"))
    )
    (net (code "54") (name "TX0") (class "Default")
      (node (ref "U2") (pin "1") (pinfunction "TXD_1") (pintype "output"))
      (node (ref "U3") (pin "9") (pinfunction "PD0(RX0)_9") (pintype "bidirectional"))
    )
    (net (code "55") (name "VCCIO") (class "Default")
      (node (ref "U2") (pin "4") (pinfunction "VCCIO_4") (pintype "power_in"))
    )
    (net (code "56") (name "V_BAT") (class "Default")
      (node (ref "C7") (pin "1") (pinfunction "1_1") (pintype "passive"))
      (node (ref "J3") (pin "PWR") (pinfunction "PIN2_PWR") (pintype "bidirectional"))
      (node (ref "Q1") (pin "1") (pinfunction "G_1") (pintype "passive"))
      (node (ref "Q3") (pin "3") (pinfunction "D_3") (pintype "passive"))
      (node (ref "U6") (pin "2") (pinfunction "VIN_2") (pintype "bidirectional"))
      (node (ref "U6") (pin "3") (pinfunction "EN_3") (pintype "bidirectional"))
    )
    (net (code "57") (name "unconnected-(J1-ID-Pad4)") (class "Default")
      (node (ref "J1") (pin "4") (pinfunction "ID_4") (pintype "bidirectional"))
    )
    (net (code "58") (name "unconnected-(SW2-Pad3)") (class "Default")
      (node (ref "SW2") (pin "3") (pinfunction "3_3") (pintype "bidirectional"))
    )
    (net (code "59") (name "unconnected-(U1-DIO1-Pad15)") (class "Default")
      (node (ref "U1") (pin "15") (pinfunction "DIO1_15") (pintype "bidirectional"))
    )
    (net (code "60") (name "unconnected-(U1-DIO2-Pad16)") (class "Default")
      (node (ref "U1") (pin "16") (pinfunction "DIO2_16") (pintype "bidirectional"))
    )
    (net (code "61") (name "unconnected-(U1-DIO3-Pad11)") (class "Default")
      (node (ref "U1") (pin "11") (pinfunction "DIO3_11") (pintype "bidirectional"))
    )
    (net (code "62") (name "unconnected-(U1-DIO4-Pad12)") (class "Default")
      (node (ref "U1") (pin "12") (pinfunction "DIO4_12") (pintype "bidirectional"))
    )
    (net (code "63") (name "unconnected-(U1-DIO5-Pad7)") (class "Default")
      (node (ref "U1") (pin "7") (pinfunction "DIO5_7") (pintype "bidirectional"))
    )
    (net (code "64") (name "unconnected-(U1-RESET-Pad6)") (class "Default")
      (node (ref "U1") (pin "6") (pinfunction "RESET_6") (pintype "input"))
    )
    (net (code "65") (name "unconnected-(U2-CTS-Pad11)") (class "Default")
      (node (ref "U2") (pin "11") (pinfunction "CTS_11") (pintype "bidirectional"))
    )
    (net (code "66") (name "unconnected-(U2-RTS-Pad3)") (class "Default")
      (node (ref "U2") (pin "3") (pinfunction "RTS_3") (pintype "bidirectional"))
    )
    (net (code "67") (name "unconnected-(U3-AREF-Pad29)") (class "Default")
      (node (ref "U3") (pin "29") (pinfunction "AREF_29") (pintype "bidirectional"))
    )
    (net (code "68") (name "unconnected-(U3-PA0(ADC0)-Pad37)") (class "Default")
      (node (ref "U3") (pin "37") (pinfunction "PA0(ADC0)_37") (pintype "bidirectional"))
    )
    (net (code "69") (name "unconnected-(U3-PA1(ADC1)-Pad36)") (class "Default")
      (node (ref "U3") (pin "36") (pinfunction "PA1(ADC1)_36") (pintype "bidirectional"))
    )
    (net (code "70") (name "unconnected-(U3-PA2(ADC2)-Pad35)") (class "Default")
      (node (ref "U3") (pin "35") (pinfunction "PA2(ADC2)_35") (pintype "bidirectional"))
    )
    (net (code "71") (name "unconnected-(U3-PA3(ADC3)-Pad34)") (class "Default")
      (node (ref "U3") (pin "34") (pinfunction "PA3(ADC3)_34") (pintype "bidirectional"))
    )
    (net (code "72") (name "unconnected-(U3-PA4(ADC4)-Pad33)") (class "Default")
      (node (ref "U3") (pin "33") (pinfunction "PA4(ADC4)_33") (pintype "bidirectional"))
    )
    (net (code "73") (name "unconnected-(U3-PA5(ADC5)-Pad32)") (class "Default")
      (node (ref "U3") (pin "32") (pinfunction "PA5(ADC5)_32") (pintype "bidirectional"))
    )
    (net (code "74") (name "unconnected-(U3-PA6(ADC6)-Pad31)") (class "Default")
      (node (ref "U3") (pin "31") (pinfunction "PA6(ADC6)_31") (pintype "bidirectional"))
    )
    (net (code "75") (name "unconnected-(U3-PA7(ADC7)-Pad30)") (class "Default")
      (node (ref "U3") (pin "30") (pinfunction "PA7(ADC7)_30") (pintype "bidirectional"))
    )
    (net (code "76") (name "unconnected-(U3-PD3(INT1{slash}TX1)-Pad12)") (class "Default")
      (node (ref "U3") (pin "12") (pinfunction "PD3(INT1/TX1)_12") (pintype "bidirectional"))
    )
    (net (code "77") (name "unconnected-(U4-32K-Pad1)") (class "Default")
      (node (ref "U4") (pin "1") (pinfunction "32K_1") (pintype "bidirectional"))
    )
    (net (code "78") (name "unconnected-(U4-RST-Pad4)") (class "Default")
      (node (ref "U4") (pin "4") (pinfunction "RST_4") (pintype "bidirectional"))
    )
  )
)
